# CNC_Remote.net
KiCad netlist of a schematic drawn in Altium Designer
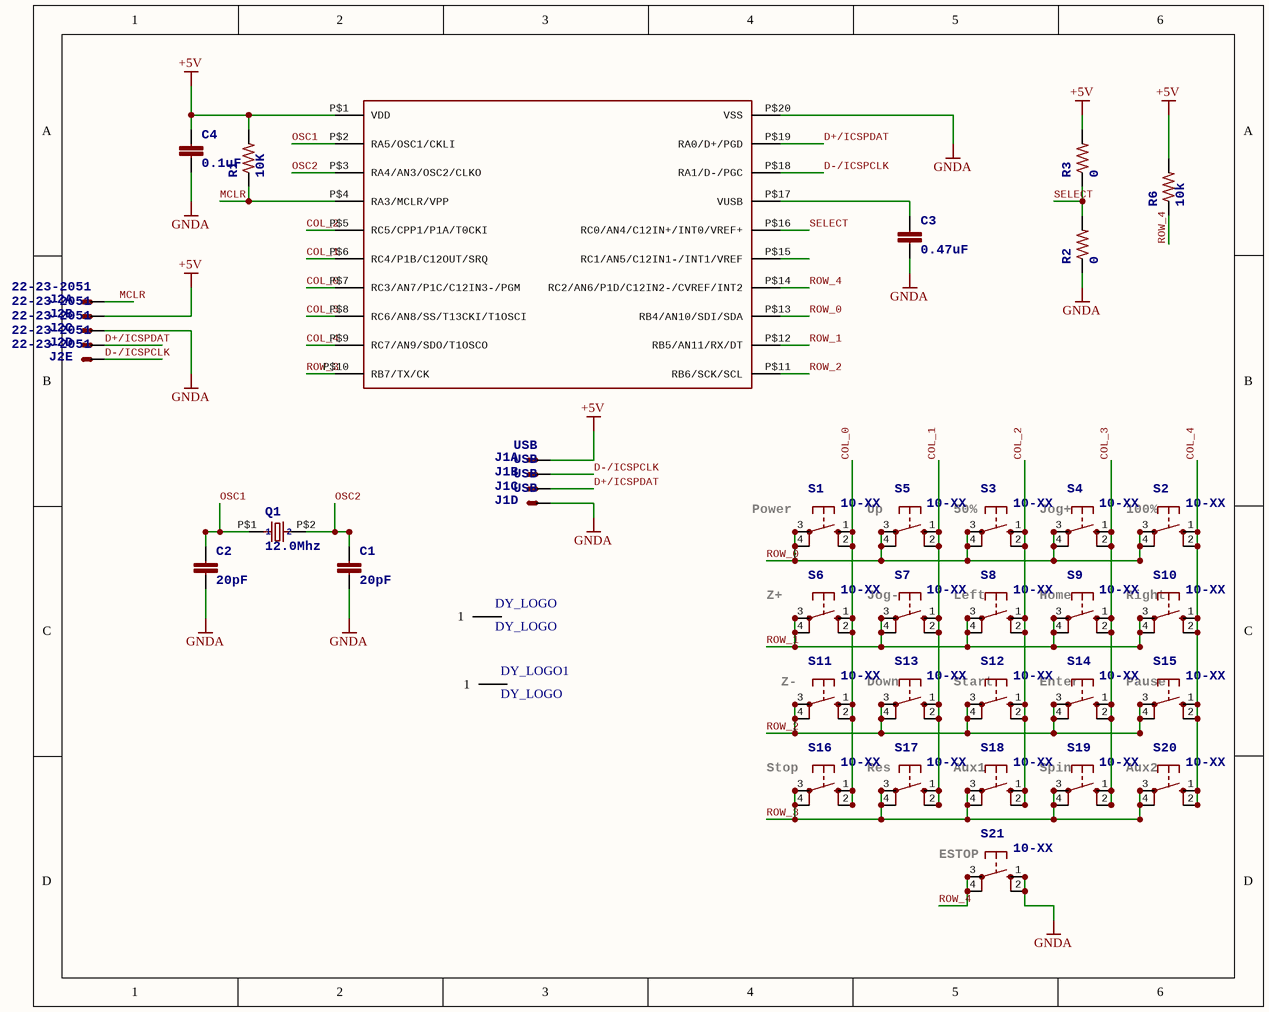
[diagram p0: CNC_Remote.SchDoc]

(export (version "E")
  (design (tool "Eeschema 10.0.6"))
  (components
    (comp (ref "C1")
      (value "20pF")
      (footprint "C0805")
      (description "<B>CAPACITOR</B>, European symbol")
      (libsource (lib "rcl") (part "C-EUC0603"))
    )
    (comp (ref "C2")
      (value "20pF")
      (footprint "C0805")
      (description "<B>CAPACITOR</B>, European symbol")
      (libsource (lib "rcl") (part "C-EUC0603"))
    )
    (comp (ref "C3")
      (value "0.47uF")
      (footprint "C0805")
      (description "<B>CAPACITOR</B>, European symbol")
      (libsource (lib "rcl") (part "C-EUC0603"))
    )
    (comp (ref "C4")
      (value "0.1uF")
      (footprint "C0805")
      (description "<B>CAPACITOR</B>, European symbol")
      (libsource (lib "rcl") (part "C-EUC0603"))
    )
    (comp (ref "DY_LOGO") (value "DY_LOGO") (footprint "DY_logo") (libsource (lib "Thach") (part "DY_LOGO")))
    (comp (ref "DY_LOGO1") (value "DY_LOGO") (footprint "DY_logo") (libsource (lib "Thach") (part "DY_LOGO")))
    (comp (ref "J1")
      (value "USB")
      (footprint "22-23-2041")
      (description ".100\" (2.54mm) Center Header - 4 Pin")
      (fields (field (name "MF") "MOLEX") (field (name "MPN") "22-23-2041"))
      (libsource (lib "con-molex") (part "22-23-2041"))
    )
    (comp (ref "J2")
      (value "22-23-2051")
      (footprint "22-23-2051")
      (description ".100\" (2.54mm) Center Header - 5 Pin")
      (fields (field (name "MF") "MOLEX"))
      (libsource (lib "con-molex") (part "22-23-2051"))
    )
    (comp (ref "Q1")
      (value "12.0Mhz")
      (footprint "HC49/US")
      (fields (field (name "1") "1") (field (name "2") "2"))
      (libsource (lib "crystal") (part "CSM-3X"))
    )
    (comp (ref "R1")
      (value "10K")
      (footprint "R0805")
      (description "<B>RESISTOR</B>, American symbol")
      (libsource (lib "rcl") (part "R-US_R0603"))
    )
    (comp (ref "R2")
      (value "0")
      (footprint "R0805")
      (description "<B>RESISTOR</B>, American symbol")
      (libsource (lib "rcl") (part "R-US_R0603"))
    )
    (comp (ref "R3")
      (value "0")
      (footprint "R0805")
      (description "<B>RESISTOR</B>, American symbol")
      (libsource (lib "rcl") (part "R-US_R0603"))
    )
    (comp (ref "R6")
      (value "10k")
      (footprint "R0805")
      (description "<B>RESISTOR</B>, American symbol")
      (libsource (lib "rcl") (part "R-US_R0603"))
    )
    (comp (ref "S1")
      (value "10-XX")
      (footprint "B3F-10XX")
      (description "<b>OMRON SWITCH</b>")
      (fields (field (name "MPN") "B3F-1000"))
      (libsource (lib "switch-omron") (part "10-XX"))
    )
    (comp (ref "S2")
      (value "10-XX")
      (footprint "B3F-10XX")
      (description "<b>OMRON SWITCH</b>")
      (fields (field (name "MPN") "B3F-1000"))
      (libsource (lib "switch-omron") (part "10-XX"))
    )
    (comp (ref "S3")
      (value "10-XX")
      (footprint "B3F-10XX")
      (description "<b>OMRON SWITCH</b>")
      (fields (field (name "MPN") "B3F-1000"))
      (libsource (lib "switch-omron") (part "10-XX"))
    )
    (comp (ref "S4")
      (value "10-XX")
      (footprint "B3F-10XX")
      (description "<b>OMRON SWITCH</b>")
      (fields (field (name "MPN") "B3F-1000"))
      (libsource (lib "switch-omron") (part "10-XX"))
    )
    (comp (ref "S5")
      (value "10-XX")
      (footprint "B3F-10XX")
      (description "<b>OMRON SWITCH</b>")
      (fields (field (name "MPN") "B3F-1000"))
      (libsource (lib "switch-omron") (part "10-XX"))
    )
    (comp (ref "S6")
      (value "10-XX")
      (footprint "B3F-10XX")
      (description "<b>OMRON SWITCH</b>")
      (fields (field (name "MPN") "B3F-1000"))
      (libsource (lib "switch-omron") (part "10-XX"))
    )
    (comp (ref "S7")
      (value "10-XX")
      (footprint "B3F-10XX")
      (description "<b>OMRON SWITCH</b>")
      (fields (field (name "MPN") "B3F-1000"))
      (libsource (lib "switch-omron") (part "10-XX"))
    )
    (comp (ref "S8")
      (value "10-XX")
      (footprint "B3F-10XX")
      (description "<b>OMRON SWITCH</b>")
      (fields (field (name "MPN") "B3F-1000"))
      (libsource (lib "switch-omron") (part "10-XX"))
    )
    (comp (ref "S9")
      (value "10-XX")
      (footprint "B3F-10XX")
      (description "<b>OMRON SWITCH</b>")
      (fields (field (name "MPN") "B3F-1000"))
      (libsource (lib "switch-omron") (part "10-XX"))
    )
    (comp (ref "S10")
      (value "10-XX")
      (footprint "B3F-10XX")
      (description "<b>OMRON SWITCH</b>")
      (fields (field (name "MPN") "B3F-1000"))
      (libsource (lib "switch-omron") (part "10-XX"))
    )
    (comp (ref "S11")
      (value "10-XX")
      (footprint "B3F-10XX")
      (description "<b>OMRON SWITCH</b>")
      (fields (field (name "MPN") "B3F-1000"))
      (libsource (lib "switch-omron") (part "10-XX"))
    )
    (comp (ref "S12")
      (value "10-XX")
      (footprint "B3F-10XX")
      (description "<b>OMRON SWITCH</b>")
      (fields (field (name "MPN") "B3F-1000"))
      (libsource (lib "switch-omron") (part "10-XX"))
    )
    (comp (ref "S13")
      (value "10-XX")
      (footprint "B3F-10XX")
      (description "<b>OMRON SWITCH</b>")
      (fields (field (name "MPN") "B3F-1000"))
      (libsource (lib "switch-omron") (part "10-XX"))
    )
    (comp (ref "S14")
      (value "10-XX")
      (footprint "B3F-10XX")
      (description "<b>OMRON SWITCH</b>")
      (fields (field (name "MPN") "B3F-1000"))
      (libsource (lib "switch-omron") (part "10-XX"))
    )
    (comp (ref "S15")
      (value "10-XX")
      (footprint "B3F-10XX")
      (description "<b>OMRON SWITCH</b>")
      (fields (field (name "MPN") "B3F-1000"))
      (libsource (lib "switch-omron") (part "10-XX"))
    )
    (comp (ref "S16")
      (value "10-XX")
      (footprint "B3F-10XX")
      (description "<b>OMRON SWITCH</b>")
      (fields (field (name "MPN") "B3F-1000"))
      (libsource (lib "switch-omron") (part "10-XX"))
    )
    (comp (ref "S17")
      (value "10-XX")
      (footprint "B3F-10XX")
      (description "<b>OMRON SWITCH</b>")
      (fields (field (name "MPN") "B3F-1000"))
      (libsource (lib "switch-omron") (part "10-XX"))
    )
    (comp (ref "S18")
      (value "10-XX")
      (footprint "B3F-10XX")
      (description "<b>OMRON SWITCH</b>")
      (fields (field (name "MPN") "B3F-1000"))
      (libsource (lib "switch-omron") (part "10-XX"))
    )
    (comp (ref "S19")
      (value "10-XX")
      (footprint "B3F-10XX")
      (description "<b>OMRON SWITCH</b>")
      (fields (field (name "MPN") "B3F-1000"))
      (libsource (lib "switch-omron") (part "10-XX"))
    )
    (comp (ref "S20")
      (value "10-XX")
      (footprint "B3F-10XX")
      (description "<b>OMRON SWITCH</b>")
      (fields (field (name "MPN") "B3F-1000"))
      (libsource (lib "switch-omron") (part "10-XX"))
    )
    (comp (ref "S21")
      (value "10-XX")
      (footprint "B3F-10XX")
      (description "<b>OMRON SWITCH</b>")
      (fields (field (name "MPN") "B3F-1000"))
      (libsource (lib "switch-omron") (part "10-XX"))
    )
    (comp (ref "U1")
      (value "PIC18F1*K50SOIC")
      (footprint "SOIC-20")
      (libsource (lib "microchip") (part "PIC18F1*K50SOIC"))
    )
  )
  (nets
    (net (code "1") (name "+5V") (class "Default")
      (node (ref "C4") (pin "1") (pinfunction "1_1") (pintype "passive"))
      (node (ref "J1") (pin "1") (pinfunction "S_1") (pintype "passive"))
      (node (ref "J2") (pin "2") (pinfunction "S_2") (pintype "passive"))
      (node (ref "R1") (pin "2") (pinfunction "2_2") (pintype "passive"))
      (node (ref "R3") (pin "2") (pinfunction "2_2") (pintype "passive"))
      (node (ref "R6") (pin "2") (pinfunction "2_2") (pintype "passive"))
      (node (ref "U1") (pin "P$1") (pinfunction "VDD_P$1") (pintype "passive"))
    )
    (net (code "2") (name "/COL_0") (class "Default")
      (node (ref "S1") (pin "1") (pinfunction "S_1") (pintype "passive"))
      (node (ref "S1") (pin "2") (pinfunction "S1_2") (pintype "passive"))
      (node (ref "S11") (pin "1") (pinfunction "S_1") (pintype "passive"))
      (node (ref "S11") (pin "2") (pinfunction "S1_2") (pintype "passive"))
      (node (ref "S16") (pin "1") (pinfunction "S_1") (pintype "passive"))
      (node (ref "S16") (pin "2") (pinfunction "S1_2") (pintype "passive"))
      (node (ref "S6") (pin "1") (pinfunction "S_1") (pintype "passive"))
      (node (ref "S6") (pin "2") (pinfunction "S1_2") (pintype "passive"))
      (node (ref "U1") (pin "P$7") (pinfunction "RC3/AN7/P1C/C12IN3-/PGM_P$7") (pintype "passive"))
    )
    (net (code "3") (name "/COL_1") (class "Default")
      (node (ref "S13") (pin "1") (pinfunction "S_1") (pintype "passive"))
      (node (ref "S13") (pin "2") (pinfunction "S1_2") (pintype "passive"))
      (node (ref "S17") (pin "1") (pinfunction "S_1") (pintype "passive"))
      (node (ref "S17") (pin "2") (pinfunction "S1_2") (pintype "passive"))
      (node (ref "S5") (pin "1") (pinfunction "S_1") (pintype "passive"))
      (node (ref "S5") (pin "2") (pinfunction "S1_2") (pintype "passive"))
      (node (ref "S7") (pin "1") (pinfunction "S_1") (pintype "passive"))
      (node (ref "S7") (pin "2") (pinfunction "S1_2") (pintype "passive"))
      (node (ref "U1") (pin "P$6") (pinfunction "RC4/P1B/C12OUT/SRQ_P$6") (pintype "passive"))
    )
    (net (code "4") (name "/COL_2") (class "Default")
      (node (ref "S12") (pin "1") (pinfunction "S_1") (pintype "passive"))
      (node (ref "S12") (pin "2") (pinfunction "S1_2") (pintype "passive"))
      (node (ref "S18") (pin "1") (pinfunction "S_1") (pintype "passive"))
      (node (ref "S18") (pin "2") (pinfunction "S1_2") (pintype "passive"))
      (node (ref "S3") (pin "1") (pinfunction "S_1") (pintype "passive"))
      (node (ref "S3") (pin "2") (pinfunction "S1_2") (pintype "passive"))
      (node (ref "S8") (pin "1") (pinfunction "S_1") (pintype "passive"))
      (node (ref "S8") (pin "2") (pinfunction "S1_2") (pintype "passive"))
      (node (ref "U1") (pin "P$5") (pinfunction "RC5/CPP1/P1A/T0CKI_P$5") (pintype "passive"))
    )
    (net (code "5") (name "/COL_3") (class "Default")
      (node (ref "S14") (pin "1") (pinfunction "S_1") (pintype "passive"))
      (node (ref "S14") (pin "2") (pinfunction "S1_2") (pintype "passive"))
      (node (ref "S19") (pin "1") (pinfunction "S_1") (pintype "passive"))
      (node (ref "S19") (pin "2") (pinfunction "S1_2") (pintype "passive"))
      (node (ref "S4") (pin "1") (pinfunction "S_1") (pintype "passive"))
      (node (ref "S4") (pin "2") (pinfunction "S1_2") (pintype "passive"))
      (node (ref "S9") (pin "1") (pinfunction "S_1") (pintype "passive"))
      (node (ref "S9") (pin "2") (pinfunction "S1_2") (pintype "passive"))
      (node (ref "U1") (pin "P$8") (pinfunction "RC6/AN8/SS/T13CKI/T1OSCI_P$8") (pintype "passive"))
    )
    (net (code "6") (name "/COL_4") (class "Default")
      (node (ref "S10") (pin "1") (pinfunction "S_1") (pintype "passive"))
      (node (ref "S10") (pin "2") (pinfunction "S1_2") (pintype "passive"))
      (node (ref "S15") (pin "1") (pinfunction "S_1") (pintype "passive"))
      (node (ref "S15") (pin "2") (pinfunction "S1_2") (pintype "passive"))
      (node (ref "S2") (pin "1") (pinfunction "S_1") (pintype "passive"))
      (node (ref "S2") (pin "2") (pinfunction "S1_2") (pintype "passive"))
      (node (ref "S20") (pin "1") (pinfunction "S_1") (pintype "passive"))
      (node (ref "S20") (pin "2") (pinfunction "S1_2") (pintype "passive"))
      (node (ref "U1") (pin "P$9") (pinfunction "RC7/AN9/SDO/T1OSCO_P$9") (pintype "passive"))
    )
    (net (code "7") (name "/D+{slash}ICSPDAT") (class "Default")
      (node (ref "J1") (pin "3") (pinfunction "S_3") (pintype "passive"))
      (node (ref "J2") (pin "4") (pinfunction "S_4") (pintype "passive"))
      (node (ref "U1") (pin "P$19") (pinfunction "RA0/D+/PGD_P$19") (pintype "passive"))
    )
    (net (code "8") (name "/D-{slash}ICSPCLK") (class "Default")
      (node (ref "J1") (pin "2") (pinfunction "S_2") (pintype "passive"))
      (node (ref "J2") (pin "5") (pinfunction "S_5") (pintype "passive"))
      (node (ref "U1") (pin "P$18") (pinfunction "RA1/D-/PGC_P$18") (pintype "passive"))
    )
    (net (code "9") (name "/MCLR") (class "Default")
      (node (ref "J2") (pin "1") (pinfunction "S_1") (pintype "passive"))
      (node (ref "R1") (pin "1") (pinfunction "1_1") (pintype "passive"))
      (node (ref "U1") (pin "P$4") (pinfunction "RA3/MCLR/VPP_P$4") (pintype "passive"))
    )
    (net (code "10") (name "/OSC1") (class "Default")
      (node (ref "C2") (pin "1") (pinfunction "1_1") (pintype "passive"))
      (node (ref "Q1") (pin "P$1") (pinfunction "1_P$1") (pintype "passive"))
      (node (ref "U1") (pin "P$2") (pinfunction "RA5/OSC1/CKLI_P$2") (pintype "passive"))
    )
    (net (code "11") (name "/OSC2") (class "Default")
      (node (ref "C1") (pin "1") (pinfunction "1_1") (pintype "passive"))
      (node (ref "Q1") (pin "P$2") (pinfunction "2_P$2") (pintype "passive"))
      (node (ref "U1") (pin "P$3") (pinfunction "RA4/AN3/OSC2/CLKO_P$3") (pintype "passive"))
    )
    (net (code "12") (name "/ROW_0") (class "Default")
      (node (ref "S1") (pin "3") (pinfunction "P_3") (pintype "passive"))
      (node (ref "S1") (pin "4") (pinfunction "P1_4") (pintype "passive"))
      (node (ref "S2") (pin "3") (pinfunction "P_3") (pintype "passive"))
      (node (ref "S2") (pin "4") (pinfunction "P1_4") (pintype "passive"))
      (node (ref "S3") (pin "3") (pinfunction "P_3") (pintype "passive"))
      (node (ref "S3") (pin "4") (pinfunction "P1_4") (pintype "passive"))
      (node (ref "S4") (pin "3") (pinfunction "P_3") (pintype "passive"))
      (node (ref "S4") (pin "4") (pinfunction "P1_4") (pintype "passive"))
      (node (ref "S5") (pin "3") (pinfunction "P_3") (pintype "passive"))
      (node (ref "S5") (pin "4") (pinfunction "P1_4") (pintype "passive"))
      (node (ref "U1") (pin "P$13") (pinfunction "RB4/AN10/SDI/SDA_P$13") (pintype "passive"))
    )
    (net (code "13") (name "/ROW_1") (class "Default")
      (node (ref "S10") (pin "3") (pinfunction "P_3") (pintype "passive"))
      (node (ref "S10") (pin "4") (pinfunction "P1_4") (pintype "passive"))
      (node (ref "S6") (pin "3") (pinfunction "P_3") (pintype "passive"))
      (node (ref "S6") (pin "4") (pinfunction "P1_4") (pintype "passive"))
      (node (ref "S7") (pin "3") (pinfunction "P_3") (pintype "passive"))
      (node (ref "S7") (pin "4") (pinfunction "P1_4") (pintype "passive"))
      (node (ref "S8") (pin "3") (pinfunction "P_3") (pintype "passive"))
      (node (ref "S8") (pin "4") (pinfunction "P1_4") (pintype "passive"))
      (node (ref "S9") (pin "3") (pinfunction "P_3") (pintype "passive"))
      (node (ref "S9") (pin "4") (pinfunction "P1_4") (pintype "passive"))
      (node (ref "U1") (pin "P$12") (pinfunction "RB5/AN11/RX/DT_P$12") (pintype "passive"))
    )
    (net (code "14") (name "/ROW_2") (class "Default")
      (node (ref "S11") (pin "3") (pinfunction "P_3") (pintype "passive"))
      (node (ref "S11") (pin "4") (pinfunction "P1_4") (pintype "passive"))
      (node (ref "S12") (pin "3") (pinfunction "P_3") (pintype "passive"))
      (node (ref "S12") (pin "4") (pinfunction "P1_4") (pintype "passive"))
      (node (ref "S13") (pin "3") (pinfunction "P_3") (pintype "passive"))
      (node (ref "S13") (pin "4") (pinfunction "P1_4") (pintype "passive"))
      (node (ref "S14") (pin "3") (pinfunction "P_3") (pintype "passive"))
      (node (ref "S14") (pin "4") (pinfunction "P1_4") (pintype "passive"))
      (node (ref "S15") (pin "3") (pinfunction "P_3") (pintype "passive"))
      (node (ref "S15") (pin "4") (pinfunction "P1_4") (pintype "passive"))
      (node (ref "U1") (pin "P$11") (pinfunction "RB6/SCK/SCL_P$11") (pintype "passive"))
    )
    (net (code "15") (name "/ROW_3") (class "Default")
      (node (ref "S16") (pin "3") (pinfunction "P_3") (pintype "passive"))
      (node (ref "S16") (pin "4") (pinfunction "P1_4") (pintype "passive"))
      (node (ref "S17") (pin "3") (pinfunction "P_3") (pintype "passive"))
      (node (ref "S17") (pin "4") (pinfunction "P1_4") (pintype "passive"))
      (node (ref "S18") (pin "3") (pinfunction "P_3") (pintype "passive"))
      (node (ref "S18") (pin "4") (pinfunction "P1_4") (pintype "passive"))
      (node (ref "S19") (pin "3") (pinfunction "P_3") (pintype "passive"))
      (node (ref "S19") (pin "4") (pinfunction "P1_4") (pintype "passive"))
      (node (ref "S20") (pin "3") (pinfunction "P_3") (pintype "passive"))
      (node (ref "S20") (pin "4") (pinfunction "P1_4") (pintype "passive"))
      (node (ref "U1") (pin "P$10") (pinfunction "RB7/TX/CK_P$10") (pintype "passive"))
    )
    (net (code "16") (name "/ROW_4") (class "Default")
      (node (ref "R6") (pin "1") (pinfunction "1_1") (pintype "passive"))
      (node (ref "S21") (pin "3") (pinfunction "P_3") (pintype "passive"))
      (node (ref "S21") (pin "4") (pinfunction "P1_4") (pintype "passive"))
      (node (ref "U1") (pin "P$14") (pinfunction "RC2/AN6/P1D/C12IN2-/CVREF/INT2_P$14") (pintype "passive"))
    )
    (net (code "17") (name "/SELECT") (class "Default")
      (node (ref "R2") (pin "2") (pinfunction "2_2") (pintype "passive"))
      (node (ref "R3") (pin "1") (pinfunction "1_1") (pintype "passive"))
      (node (ref "U1") (pin "P$16") (pinfunction "RC0/AN4/C12IN+/INT0/VREF+_P$16") (pintype "passive"))
    )
    (net (code "18") (name "GNDA") (class "Default")
      (node (ref "C1") (pin "2") (pinfunction "2_2") (pintype "passive"))
      (node (ref "C2") (pin "2") (pinfunction "2_2") (pintype "passive"))
      (node (ref "C3") (pin "2") (pinfunction "2_2") (pintype "passive"))
      (node (ref "C4") (pin "2") (pinfunction "2_2") (pintype "passive"))
      (node (ref "J1") (pin "4") (pinfunction "S_4") (pintype "passive"))
      (node (ref "J2") (pin "3") (pinfunction "S_3") (pintype "passive"))
      (node (ref "R2") (pin "1") (pinfunction "1_1") (pintype "passive"))
      (node (ref "S21") (pin "1") (pinfunction "S_1") (pintype "passive"))
      (node (ref "S21") (pin "2") (pinfunction "S1_2") (pintype "passive"))
      (node (ref "U1") (pin "P$20") (pinfunction "VSS_P$20") (pintype "passive"))
    )
    (net (code "19") (name "Net-(U1-VUSB)") (class "Default")
      (node (ref "C3") (pin "1") (pinfunction "1_1") (pintype "passive"))
      (node (ref "U1") (pin "P$17") (pinfunction "VUSB_P$17") (pintype "passive"))
    )
    (net (code "20") (name "unconnected-(DY_LOGO-Pad1)") (class "Default")
      (node (ref "DY_LOGO") (pin "1") (pinfunction "1_1") (pintype "passive"))
    )
    (net (code "21") (name "unconnected-(DY_LOGO1-Pad1)") (class "Default")
      (node (ref "DY_LOGO1") (pin "1") (pinfunction "1_1") (pintype "passive"))
    )
    (net (code "22") (name "unconnected-(U1-RC1{slash}AN5{slash}C12IN1-{slash}INT1{slash}VREF-PadP$15)") (class "Default")
      (node (ref "U1") (pin "P$15") (pinfunction "RC1/AN5/C12IN1-/INT1/VREF_P$15") (pintype "passive"))
    )
  )
)
